# ALU_ONES.net
KiCad netlist of a schematic drawn in Altium Designer
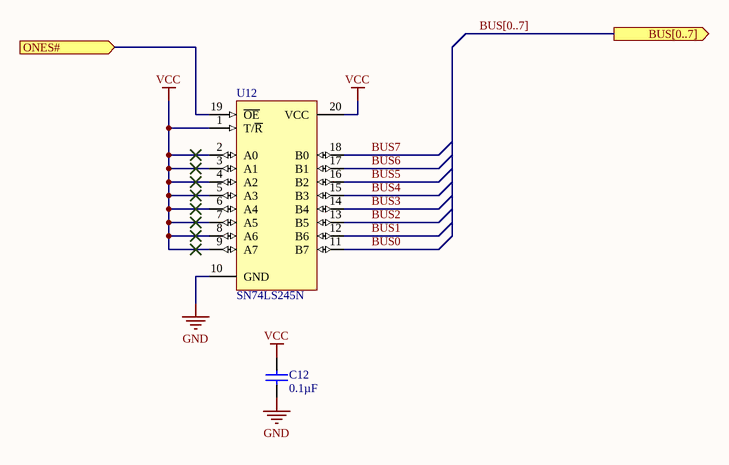
[diagram p0: ALU_ONES.SchDoc]

(export (version "E")
  (design (tool "Eeschema 10.0.6"))
  (components
    (comp (ref "C12")
      (value "K104K15X7RF5TL2")
      (footprint "VISH-K104K15X7RF5TL2")
      (description "Ceramic Capacitor, 100 nF, +/- 10%, 50 V, -55 to 125 degC, 2-Pin THD, RoHS, Tape and Reel")
      (fields
        (field (name "MANUFACTURER") "Vishay")
        (field (name "TOLERANCE") "±10%")
        (field (name "CAPACITANCE") "0.1µF")
      )
      (libsource (lib "Altium Content Vault") (part "CAP-NP-2"))
    )
    (comp (ref "U12")
      (value "SN74LS245N")
      (footprint "N020")
      (description "Octal Bus Transceiver with 3-State Outputs")
      (fields (field (name "PUBLISHER") "Altium Limited"))
      (libsource (lib "TI Interface 8-Bit Line Transceiver") (part "SN74LS245N"))
    )
  )
  (nets
    (net (code "1") (name "/BUS0") (class "Default")
      (node (ref "U12") (pin "11") (pinfunction "B7_11") (pintype "bidirectional"))
    )
    (net (code "2") (name "/BUS1") (class "Default")
      (node (ref "U12") (pin "12") (pinfunction "B6_12") (pintype "bidirectional"))
    )
    (net (code "3") (name "/BUS2") (class "Default")
      (node (ref "U12") (pin "13") (pinfunction "B5_13") (pintype "bidirectional"))
    )
    (net (code "4") (name "/BUS3") (class "Default")
      (node (ref "U12") (pin "14") (pinfunction "B4_14") (pintype "bidirectional"))
    )
    (net (code "5") (name "/BUS4") (class "Default")
      (node (ref "U12") (pin "15") (pinfunction "B3_15") (pintype "bidirectional"))
    )
    (net (code "6") (name "/BUS5") (class "Default")
      (node (ref "U12") (pin "16") (pinfunction "B2_16") (pintype "bidirectional"))
    )
    (net (code "7") (name "/BUS6") (class "Default")
      (node (ref "U12") (pin "17") (pinfunction "B1_17") (pintype "bidirectional"))
    )
    (net (code "8") (name "/BUS7") (class "Default")
      (node (ref "U12") (pin "18") (pinfunction "B0_18") (pintype "bidirectional"))
    )
    (net (code "10") (name "/ONES#") (class "Default")
      (node (ref "U12") (pin "19") (pinfunction "~{OE}_19") (pintype "input"))
    )
    (net (code "11") (name "GND") (class "Default")
      (node (ref "C12") (pin "2") (pinfunction "2_2") (pintype "passive"))
      (node (ref "U12") (pin "10") (pinfunction "GND_10") (pintype "power_in"))
    )
    (net (code "12") (name "VCC") (class "Default")
      (node (ref "C12") (pin "1") (pinfunction "1_1") (pintype "passive"))
      (node (ref "U12") (pin "1") (pinfunction "T/~{R}_1") (pintype "input"))
      (node (ref "U12") (pin "2") (pinfunction "A0_2") (pintype "bidirectional"))
      (node (ref "U12") (pin "20") (pinfunction "VCC_20") (pintype "power_in"))
      (node (ref "U12") (pin "3") (pinfunction "A1_3") (pintype "bidirectional"))
      (node (ref "U12") (pin "4") (pinfunction "A2_4") (pintype "bidirectional"))
      (node (ref "U12") (pin "5") (pinfunction "A3_5") (pintype "bidirectional"))
      (node (ref "U12") (pin "6") (pinfunction "A4_6") (pintype "bidirectional"))
      (node (ref "U12") (pin "7") (pinfunction "A5_7") (pintype "bidirectional"))
      (node (ref "U12") (pin "8") (pinfunction "A6_8") (pintype "bidirectional"))
      (node (ref "U12") (pin "9") (pinfunction "A7_9") (pintype "bidirectional"))
    )
  )
)
